# wagband_schematic_post_route.net
KiCad netlist of a schematic drawn in EAGLE
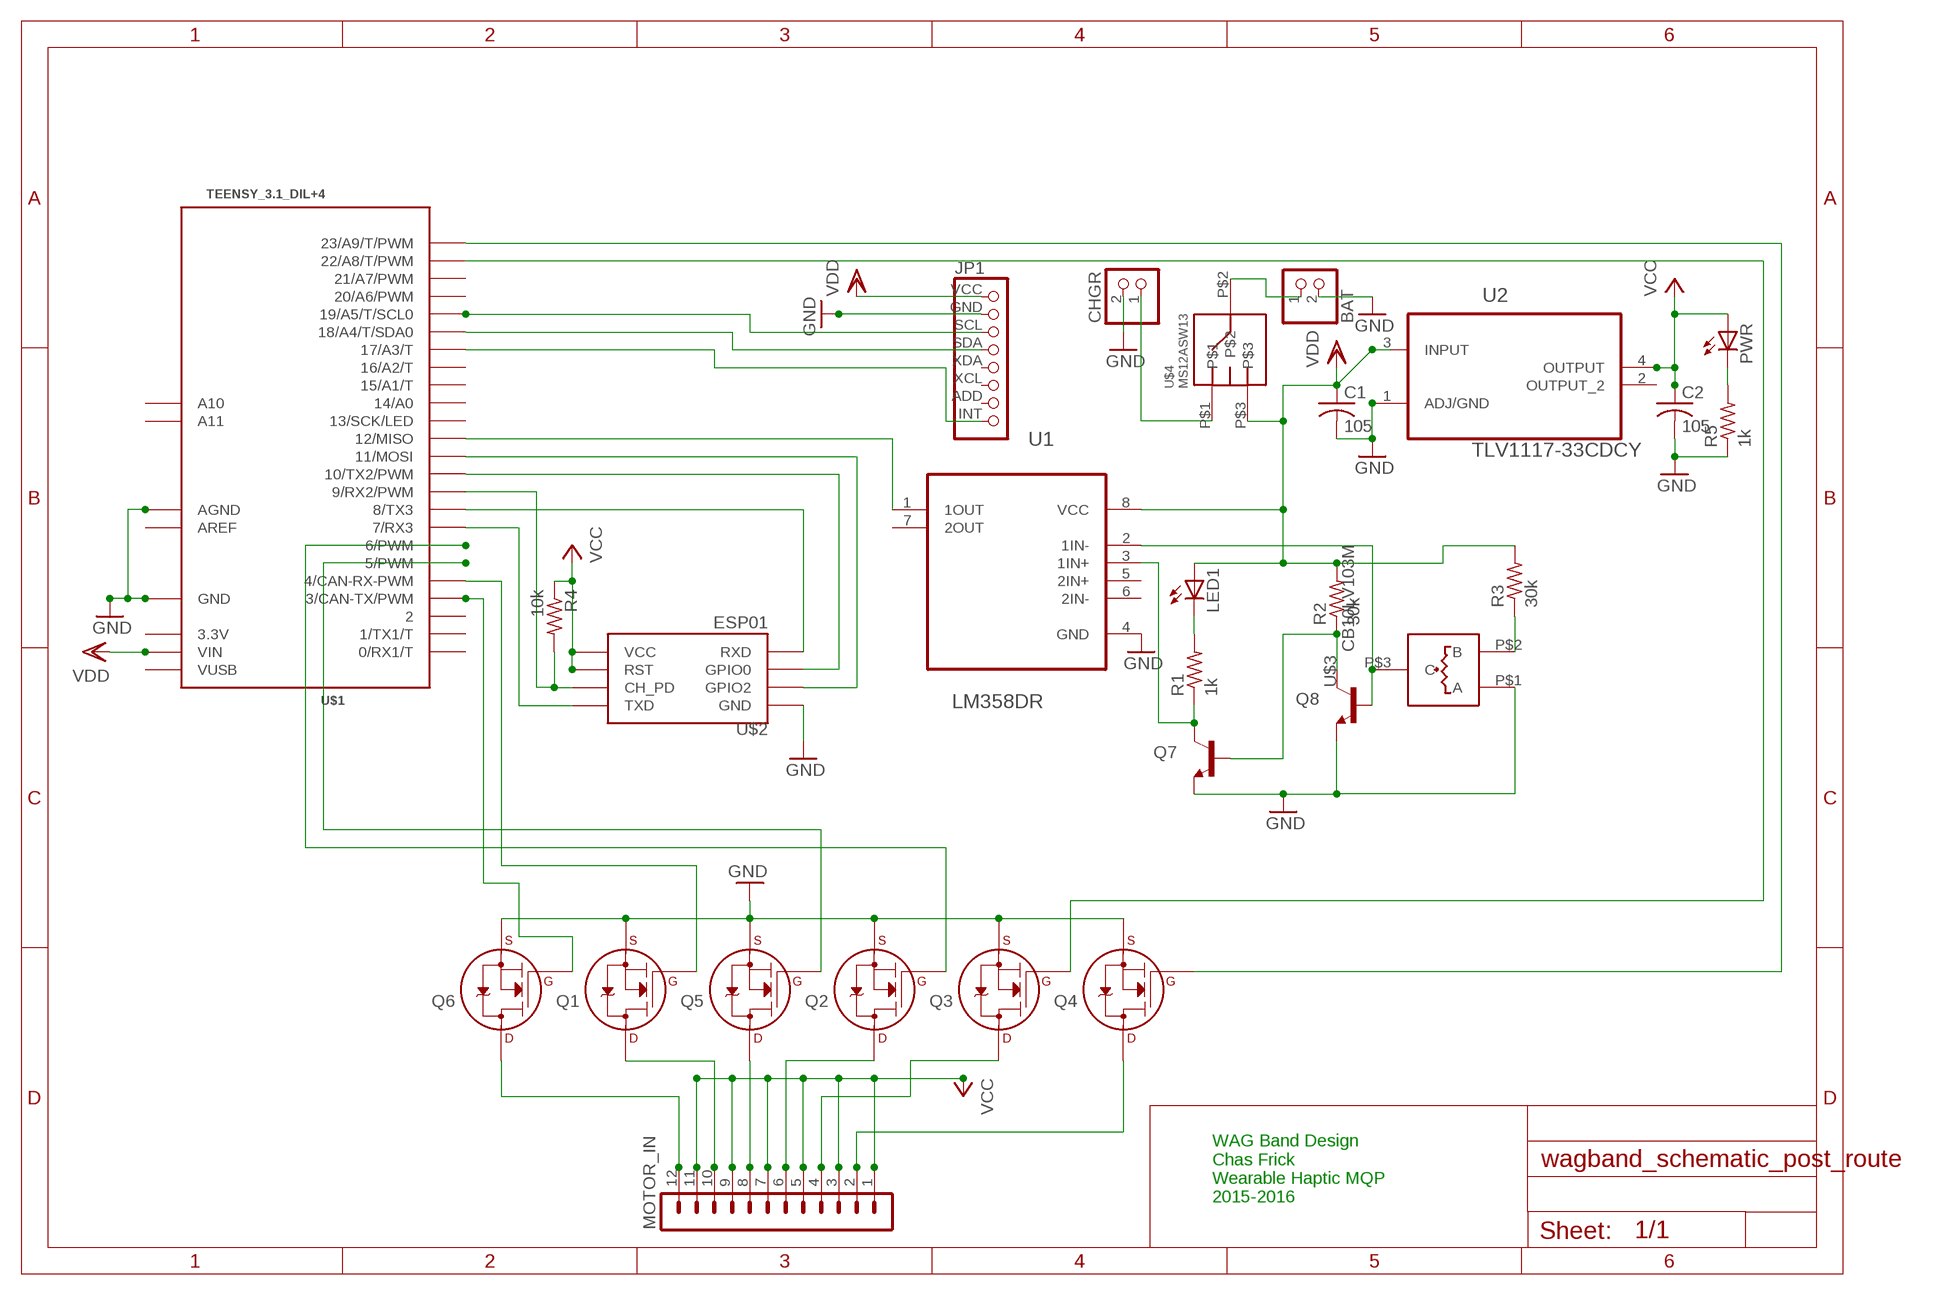
[diagram p0: schematic, sheet 1]

(export (version "E")
  (design (tool "Eeschema 10.0.6"))
  (components
    (comp (ref "BAT")
      (value "JST_2PIN-THM-RA")
      (footprint "eagle-import:JST-PH-2-THM-RA")
      (libsource (lib "eagle-import") (part "JST_2PIN-THM-RA"))
    )
    (comp (ref "C1")
      (value "105")
      (footprint "eagle-import:C0805K")
      (libsource (lib "eagle-import") (part "C-USC0805K"))
    )
    (comp (ref "C2")
      (value "105")
      (footprint "eagle-import:C0805K")
      (libsource (lib "eagle-import") (part "C-USC0805K"))
    )
    (comp (ref "CHGR")
      (value "JST_2PIN-THM-RA")
      (footprint "eagle-import:JST-PH-2-THM-RA")
      (libsource (lib "eagle-import") (part "JST_2PIN-THM-RA"))
    )
    (comp (ref "JP1")
      (value "MPU6050_BREAKOUT")
      (footprint "eagle-import:MPU6050")
      (libsource (lib "eagle-import") (part "MPU6050_BREAKOUT"))
    )
    (comp (ref "LED1")
      (value "LED5MM")
      (footprint "eagle-import:LED5MM")
      (libsource (lib "eagle-import") (part "LED5MM"))
    )
    (comp (ref "MOTOR_IN")
      (value "MA12-1W")
      (footprint "eagle-import:MA12-1W")
      (libsource (lib "eagle-import") (part "MA12-1W"))
    )
    (comp (ref "PWR")
      (value "LED5MM")
      (footprint "eagle-import:LED5MM")
      (libsource (lib "eagle-import") (part "LED5MM"))
    )
    (comp (ref "Q1")
      (value "2N7000_SOT23")
      (footprint "eagle-import:SOT-23")
      (libsource (lib "eagle-import") (part "2N700_SOT230"))
    )
    (comp (ref "Q2")
      (value "2N7000_SOT23")
      (footprint "eagle-import:SOT-23")
      (libsource (lib "eagle-import") (part "2N700_SOT230"))
    )
    (comp (ref "Q3")
      (value "2N7000_SOT23")
      (footprint "eagle-import:SOT-23")
      (libsource (lib "eagle-import") (part "2N700_SOT230"))
    )
    (comp (ref "Q4")
      (value "2N7000_SOT23")
      (footprint "eagle-import:SOT-23")
      (libsource (lib "eagle-import") (part "2N700_SOT230"))
    )
    (comp (ref "Q5")
      (value "2N7000_SOT23")
      (footprint "eagle-import:SOT-23")
      (libsource (lib "eagle-import") (part "2N700_SOT230"))
    )
    (comp (ref "Q6")
      (value "2N7000_SOT23")
      (footprint "eagle-import:SOT-23")
      (libsource (lib "eagle-import") (part "2N700_SOT230"))
    )
    (comp (ref "Q7")
      (value "TRANSISTOR_NPNMMBT3904")
      (footprint "eagle-import:SOT-23")
      (libsource (lib "eagle-import") (part "TRANSISTOR_NPNMMBT3904"))
    )
    (comp (ref "Q8")
      (value "TRANSISTOR_NPNMMBT3904")
      (footprint "eagle-import:SOT-23")
      (libsource (lib "eagle-import") (part "TRANSISTOR_NPNMMBT3904"))
    )
    (comp (ref "R1")
      (value "1k")
      (footprint "eagle-import:R1206")
      (libsource (lib "eagle-import") (part "R-US_R1206"))
    )
    (comp (ref "R2")
      (value "30k")
      (footprint "eagle-import:R1206")
      (libsource (lib "eagle-import") (part "R-US_R1206"))
    )
    (comp (ref "R3")
      (value "30k")
      (footprint "eagle-import:R1206")
      (libsource (lib "eagle-import") (part "R-US_R1206"))
    )
    (comp (ref "R4")
      (value "10k")
      (footprint "eagle-import:R1206")
      (libsource (lib "eagle-import") (part "R-US_R1206"))
    )
    (comp (ref "R5")
      (value "1k")
      (footprint "eagle-import:R1206")
      (libsource (lib "eagle-import") (part "R-US_R1206"))
    )
    (comp (ref "U$1")
      (value "TEENSY_3.1_DIL+4")
      (footprint "eagle-import:TEENSY3-DIL+4")
      (libsource (lib "eagle-import") (part "TEENSY_3.1_DIL+4"))
    )
    (comp (ref "U$2")
      (value "ESP01")
      (footprint "eagle-import:ESP01")
      (libsource (lib "eagle-import") (part "ESP01"))
    )
    (comp (ref "U$3")
      (value "CB10LV103M")
      (footprint "eagle-import:CB10")
      (libsource (lib "eagle-import") (part "CB10LV103M"))
    )
    (comp (ref "U$4")
      (value "MS12ASW13")
      (footprint "eagle-import:SPDT")
      (libsource (lib "eagle-import") (part "MS12ASW13"))
    )
    (comp (ref "U1")
      (value "LM358DR")
      (footprint "eagle-import:SOIC127P600X175-8N")
      (libsource (lib "eagle-import") (part "LM358DR"))
    )
    (comp (ref "U2")
      (value "TLV1117-33CDCY")
      (footprint "eagle-import:SOT230P700X180-4N")
      (libsource (lib "eagle-import") (part "TLV1117-33CDCY"))
    )
  )
  (nets
    (net (code "1") (name "/3.3V") (class "Default")
      (node (ref "U$1") (pin "3.3V") (pinfunction "3.3V_3.3V") (pintype "power_in"))
    )
    (net (code "2") (name "/AREF") (class "Default")
      (node (ref "U$1") (pin "AREF") (pinfunction "AREF_AREF") (pintype "power_in"))
    )
    (net (code "3") (name "/VUSB") (class "Default")
      (node (ref "U$1") (pin "VUSB") (pinfunction "VUSB_VUSB") (pintype "power_in"))
    )
    (net (code "4") (name "GND") (class "Default")
      (node (ref "BAT") (pin "2") (pinfunction "1_2") (pintype "passive"))
      (node (ref "C1") (pin "2") (pinfunction "2_2") (pintype "passive"))
      (node (ref "C2") (pin "2") (pinfunction "2_2") (pintype "passive"))
      (node (ref "CHGR") (pin "2") (pinfunction "1_2") (pintype "passive"))
      (node (ref "JP1") (pin "GND") (pinfunction "GND_GND") (pintype "passive"))
      (node (ref "Q1") (pin "2") (pinfunction "S_2") (pintype "bidirectional"))
      (node (ref "Q2") (pin "2") (pinfunction "S_2") (pintype "bidirectional"))
      (node (ref "Q3") (pin "2") (pinfunction "S_2") (pintype "bidirectional"))
      (node (ref "Q4") (pin "2") (pinfunction "S_2") (pintype "bidirectional"))
      (node (ref "Q5") (pin "2") (pinfunction "S_2") (pintype "bidirectional"))
      (node (ref "Q6") (pin "2") (pinfunction "S_2") (pintype "bidirectional"))
      (node (ref "Q7") (pin "2") (pinfunction "E_2") (pintype "passive"))
      (node (ref "Q8") (pin "2") (pinfunction "E_2") (pintype "passive"))
      (node (ref "R5") (pin "1") (pinfunction "1_1") (pintype "passive"))
      (node (ref "U$1") (pin "AGND") (pinfunction "AGND_AGND") (pintype "power_in"))
      (node (ref "U$1") (pin "GND") (pinfunction "GND_GND") (pintype "power_in"))
      (node (ref "U$2") (pin "GND") (pinfunction "GND_GND") (pintype "bidirectional"))
      (node (ref "U$3") (pin "P$1") (pinfunction "A_P$1") (pintype "bidirectional"))
      (node (ref "U1") (pin "4") (pinfunction "GND_4") (pintype "passive"))
      (node (ref "U2") (pin "1") (pinfunction "ADJ/GND_1") (pintype "input"))
    )
    (net (code "5") (name "Net-(BAT-2)") (class "Default")
      (node (ref "BAT") (pin "1") (pinfunction "2_1") (pintype "passive"))
      (node (ref "U$4") (pin "P$2") (pinfunction "P$2_P$2") (pintype "bidirectional"))
    )
    (net (code "6") (name "Net-(CHGR-2)") (class "Default")
      (node (ref "CHGR") (pin "1") (pinfunction "2_1") (pintype "passive"))
      (node (ref "U$4") (pin "P$1") (pinfunction "P$1_P$1") (pintype "bidirectional"))
    )
    (net (code "7") (name "Net-(LED1-C)") (class "Default")
      (node (ref "LED1") (pin "K") (pinfunction "C_K") (pintype "passive"))
      (node (ref "R1") (pin "2") (pinfunction "2_2") (pintype "passive"))
    )
    (net (code "8") (name "Net-(PWR-C)") (class "Default")
      (node (ref "PWR") (pin "K") (pinfunction "C_K") (pintype "passive"))
      (node (ref "R5") (pin "2") (pinfunction "2_2") (pintype "passive"))
    )
    (net (code "9") (name "Net-(Q1-D)") (class "Default")
      (node (ref "MOTOR_IN") (pin "10") (pinfunction "10_10") (pintype "passive"))
      (node (ref "Q1") (pin "3") (pinfunction "D_3") (pintype "bidirectional"))
    )
    (net (code "10") (name "Net-(Q1-G)") (class "Default")
      (node (ref "Q1") (pin "1") (pinfunction "G_1") (pintype "tri_state"))
      (node (ref "U$1") (pin "4") (pinfunction "4/CAN-RX-PWM_4") (pintype "bidirectional"))
    )
    (net (code "11") (name "Net-(Q2-D)") (class "Default")
      (node (ref "MOTOR_IN") (pin "6") (pinfunction "6_6") (pintype "passive"))
      (node (ref "Q2") (pin "3") (pinfunction "D_3") (pintype "bidirectional"))
    )
    (net (code "12") (name "Net-(Q2-G)") (class "Default")
      (node (ref "Q2") (pin "1") (pinfunction "G_1") (pintype "tri_state"))
      (node (ref "U$1") (pin "6") (pinfunction "6/PWM_6") (pintype "bidirectional"))
    )
    (net (code "13") (name "Net-(Q3-D)") (class "Default")
      (node (ref "MOTOR_IN") (pin "4") (pinfunction "4_4") (pintype "passive"))
      (node (ref "Q3") (pin "3") (pinfunction "D_3") (pintype "bidirectional"))
    )
    (net (code "14") (name "Net-(Q3-G)") (class "Default")
      (node (ref "Q3") (pin "1") (pinfunction "G_1") (pintype "tri_state"))
      (node (ref "U$1") (pin "22/A8") (pinfunction "22/A8/T/PWM_22/A8") (pintype "bidirectional"))
    )
    (net (code "15") (name "Net-(Q4-D)") (class "Default")
      (node (ref "MOTOR_IN") (pin "2") (pinfunction "2_2") (pintype "passive"))
      (node (ref "Q4") (pin "3") (pinfunction "D_3") (pintype "bidirectional"))
    )
    (net (code "16") (name "Net-(Q4-G)") (class "Default")
      (node (ref "Q4") (pin "1") (pinfunction "G_1") (pintype "tri_state"))
      (node (ref "U$1") (pin "23/A9") (pinfunction "23/A9/T/PWM_23/A9") (pintype "bidirectional"))
    )
    (net (code "17") (name "Net-(Q5-D)") (class "Default")
      (node (ref "MOTOR_IN") (pin "8") (pinfunction "8_8") (pintype "passive"))
      (node (ref "Q5") (pin "3") (pinfunction "D_3") (pintype "bidirectional"))
    )
    (net (code "18") (name "Net-(Q5-G)") (class "Default")
      (node (ref "Q5") (pin "1") (pinfunction "G_1") (pintype "tri_state"))
      (node (ref "U$1") (pin "5") (pinfunction "5/PWM_5") (pintype "bidirectional"))
    )
    (net (code "19") (name "Net-(Q6-D)") (class "Default")
      (node (ref "MOTOR_IN") (pin "12") (pinfunction "12_12") (pintype "passive"))
      (node (ref "Q6") (pin "3") (pinfunction "D_3") (pintype "bidirectional"))
    )
    (net (code "20") (name "Net-(Q6-G)") (class "Default")
      (node (ref "Q6") (pin "1") (pinfunction "G_1") (pintype "tri_state"))
      (node (ref "U$1") (pin "3") (pinfunction "3/CAN-TX/PWM_3") (pintype "bidirectional"))
    )
    (net (code "21") (name "Net-(Q7-B)") (class "Default")
      (node (ref "Q7") (pin "1") (pinfunction "B_1") (pintype "passive"))
      (node (ref "Q8") (pin "3") (pinfunction "C_3") (pintype "passive"))
      (node (ref "R2") (pin "1") (pinfunction "1_1") (pintype "passive"))
    )
    (net (code "22") (name "Net-(Q7-C)") (class "Default")
      (node (ref "Q7") (pin "3") (pinfunction "C_3") (pintype "passive"))
      (node (ref "R1") (pin "1") (pinfunction "1_1") (pintype "passive"))
      (node (ref "U1") (pin "3") (pinfunction "1IN+_3") (pintype "input"))
    )
    (net (code "23") (name "Net-(Q8-B)") (class "Default")
      (node (ref "Q8") (pin "1") (pinfunction "B_1") (pintype "passive"))
      (node (ref "U$3") (pin "P$3") (pinfunction "C_P$3") (pintype "bidirectional"))
      (node (ref "U1") (pin "2") (pinfunction "1IN-_2") (pintype "input"))
    )
    (net (code "24") (name "Net-(U$1-7{slash}RX3)") (class "Default")
      (node (ref "U$1") (pin "7") (pinfunction "7/RX3_7") (pintype "bidirectional"))
      (node (ref "U$2") (pin "TX") (pinfunction "TXD_TX") (pintype "bidirectional"))
    )
    (net (code "25") (name "Net-(U$1-8{slash}TX3)") (class "Default")
      (node (ref "U$1") (pin "8") (pinfunction "8/TX3_8") (pintype "bidirectional"))
      (node (ref "U$2") (pin "RX") (pinfunction "RXD_RX") (pintype "bidirectional"))
    )
    (net (code "26") (name "Net-(U$1-9{slash}RX2{slash}PWM)") (class "Default")
      (node (ref "R4") (pin "2") (pinfunction "2_2") (pintype "passive"))
      (node (ref "U$1") (pin "9") (pinfunction "9/RX2/PWM_9") (pintype "bidirectional"))
      (node (ref "U$2") (pin "CH_PD") (pinfunction "CH_PD_CH_PD") (pintype "bidirectional"))
    )
    (net (code "27") (name "Net-(U$1-10{slash}TX2{slash}PWM)") (class "Default")
      (node (ref "U$1") (pin "10") (pinfunction "10/TX2/PWM_10") (pintype "bidirectional"))
      (node (ref "U$2") (pin "GPIO0") (pinfunction "GPIO0_GPIO0") (pintype "bidirectional"))
    )
    (net (code "28") (name "Net-(U$1-11{slash}MOSI)") (class "Default")
      (node (ref "U$1") (pin "11") (pinfunction "11/MOSI_11") (pintype "bidirectional"))
      (node (ref "U$2") (pin "GPIO2") (pinfunction "GPIO2_GPIO2") (pintype "bidirectional"))
    )
    (net (code "29") (name "Net-(U$1-12{slash}MISO)") (class "Default")
      (node (ref "U$1") (pin "12") (pinfunction "12/MISO_12") (pintype "bidirectional"))
      (node (ref "U1") (pin "1") (pinfunction "1OUT_1") (pintype "output"))
    )
    (net (code "30") (name "Net-(U$1-17{slash}A3{slash}T)") (class "Default")
      (node (ref "JP1") (pin "INT") (pinfunction "INT_INT") (pintype "passive"))
      (node (ref "U$1") (pin "17/A3") (pinfunction "17/A3/T_17/A3") (pintype "bidirectional"))
    )
    (net (code "31") (name "Net-(U$1-18{slash}A4{slash}T{slash}SDA0)") (class "Default")
      (node (ref "JP1") (pin "SDA") (pinfunction "SDA_SDA") (pintype "passive"))
      (node (ref "U$1") (pin "18/A4") (pinfunction "18/A4/T/SDA0_18/A4") (pintype "bidirectional"))
    )
    (net (code "32") (name "Net-(U$1-19{slash}A5{slash}T{slash}SCL0)") (class "Default")
      (node (ref "JP1") (pin "SCL") (pinfunction "SCL_SCL") (pintype "passive"))
      (node (ref "U$1") (pin "19/A5") (pinfunction "19/A5/T/SCL0_19/A5") (pintype "bidirectional"))
    )
    (net (code "33") (name "Net-(U$3-B)") (class "Default")
      (node (ref "R3") (pin "1") (pinfunction "1_1") (pintype "passive"))
      (node (ref "U$3") (pin "P$2") (pinfunction "B_P$2") (pintype "bidirectional"))
    )
    (net (code "34") (name "VCC") (class "Default")
      (node (ref "C2") (pin "1") (pinfunction "1_1") (pintype "passive"))
      (node (ref "MOTOR_IN") (pin "1") (pinfunction "1_1") (pintype "passive"))
      (node (ref "MOTOR_IN") (pin "11") (pinfunction "11_11") (pintype "passive"))
      (node (ref "MOTOR_IN") (pin "3") (pinfunction "3_3") (pintype "passive"))
      (node (ref "MOTOR_IN") (pin "5") (pinfunction "5_5") (pintype "passive"))
      (node (ref "MOTOR_IN") (pin "7") (pinfunction "7_7") (pintype "passive"))
      (node (ref "MOTOR_IN") (pin "9") (pinfunction "9_9") (pintype "passive"))
      (node (ref "PWR") (pin "A") (pinfunction "A_A") (pintype "passive"))
      (node (ref "R4") (pin "1") (pinfunction "1_1") (pintype "passive"))
      (node (ref "U$2") (pin "RST") (pinfunction "RST_RST") (pintype "bidirectional"))
      (node (ref "U$2") (pin "VCC") (pinfunction "VCC_VCC") (pintype "bidirectional"))
      (node (ref "U2") (pin "4") (pinfunction "OUTPUT_4") (pintype "output"))
    )
    (net (code "35") (name "VDD") (class "Default")
      (node (ref "C1") (pin "1") (pinfunction "1_1") (pintype "passive"))
      (node (ref "JP1") (pin "VCC") (pinfunction "VCC_VCC") (pintype "passive"))
      (node (ref "LED1") (pin "A") (pinfunction "A_A") (pintype "passive"))
      (node (ref "R2") (pin "2") (pinfunction "2_2") (pintype "passive"))
      (node (ref "R3") (pin "2") (pinfunction "2_2") (pintype "passive"))
      (node (ref "U$1") (pin "VIN") (pinfunction "VIN_VIN") (pintype "power_in"))
      (node (ref "U$4") (pin "P$3") (pinfunction "P$3_P$3") (pintype "bidirectional"))
      (node (ref "U1") (pin "8") (pinfunction "VCC_8") (pintype "power_in"))
      (node (ref "U2") (pin "3") (pinfunction "INPUT_3") (pintype "input"))
    )
    (net (code "36") (name "unconnected-(JP1-PadADD)") (class "Default")
      (node (ref "JP1") (pin "ADD") (pinfunction "ADD_ADD") (pintype "passive"))
    )
    (net (code "37") (name "unconnected-(JP1-PadXCL)") (class "Default")
      (node (ref "JP1") (pin "XCL") (pinfunction "XCL_XCL") (pintype "passive"))
    )
    (net (code "38") (name "unconnected-(JP1-PadXDA)") (class "Default")
      (node (ref "JP1") (pin "XDA") (pinfunction "XDA_XDA") (pintype "passive"))
    )
    (net (code "39") (name "unconnected-(U$1-0{slash}RX1{slash}T-Pad0)") (class "Default")
      (node (ref "U$1") (pin "0") (pinfunction "0/RX1/T_0") (pintype "bidirectional"))
    )
    (net (code "40") (name "unconnected-(U$1-1{slash}TX1{slash}T-Pad1)") (class "Default")
      (node (ref "U$1") (pin "1") (pinfunction "1/TX1/T_1") (pintype "bidirectional"))
    )
    (net (code "41") (name "unconnected-(U$1-13{slash}SCK{slash}LED-Pad13)") (class "Default")
      (node (ref "U$1") (pin "13") (pinfunction "13/SCK/LED_13") (pintype "bidirectional"))
    )
    (net (code "42") (name "unconnected-(U$1-15{slash}A1{slash}T-Pad15{slash}A1)") (class "Default")
      (node (ref "U$1") (pin "15/A1") (pinfunction "15/A1/T_15/A1") (pintype "bidirectional"))
    )
    (net (code "43") (name "unconnected-(U$1-16{slash}A2{slash}T-Pad16{slash}A2)") (class "Default")
      (node (ref "U$1") (pin "16/A2") (pinfunction "16/A2/T_16/A2") (pintype "bidirectional"))
    )
    (net (code "44") (name "unconnected-(U$1-20{slash}A6{slash}PWM-Pad20{slash}A6)") (class "Default")
      (node (ref "U$1") (pin "20/A6") (pinfunction "20/A6/PWM_20/A6") (pintype "bidirectional"))
    )
    (net (code "45") (name "unconnected-(U$1-21{slash}A7{slash}PWM-Pad21{slash}A7)") (class "Default")
      (node (ref "U$1") (pin "21/A7") (pinfunction "21/A7/PWM_21/A7") (pintype "bidirectional"))
    )
    (net (code "46") (name "unconnected-(U$1-Pad2)") (class "Default")
      (node (ref "U$1") (pin "2") (pinfunction "2_2") (pintype "bidirectional"))
    )
    (net (code "47") (name "unconnected-(U$1-Pad14{slash}A0)") (class "Default")
      (node (ref "U$1") (pin "14/A0") (pinfunction "14/A0_14/A0") (pintype "bidirectional"))
    )
    (net (code "48") (name "unconnected-(U$1-PadA10)") (class "Default")
      (node (ref "U$1") (pin "A10") (pinfunction "A10_A10") (pintype "bidirectional"))
    )
    (net (code "49") (name "unconnected-(U$1-PadA11)") (class "Default")
      (node (ref "U$1") (pin "A11") (pinfunction "A11_A11") (pintype "bidirectional"))
    )
    (net (code "50") (name "unconnected-(U1-2IN+-Pad5)") (class "Default")
      (node (ref "U1") (pin "5") (pinfunction "2IN+_5") (pintype "input"))
    )
    (net (code "51") (name "unconnected-(U1-2IN--Pad6)") (class "Default")
      (node (ref "U1") (pin "6") (pinfunction "2IN-_6") (pintype "input"))
    )
    (net (code "52") (name "unconnected-(U1-2OUT-Pad7)") (class "Default")
      (node (ref "U1") (pin "7") (pinfunction "2OUT_7") (pintype "output"))
    )
    (net (code "53") (name "unconnected-(U2-OUTPUT_2-Pad2)") (class "Default")
      (node (ref "U2") (pin "2") (pinfunction "OUTPUT_2_2") (pintype "output"))
    )
  )
)
